# Adafruit_TXB0104.net
KiCad netlist of a schematic drawn in EAGLE
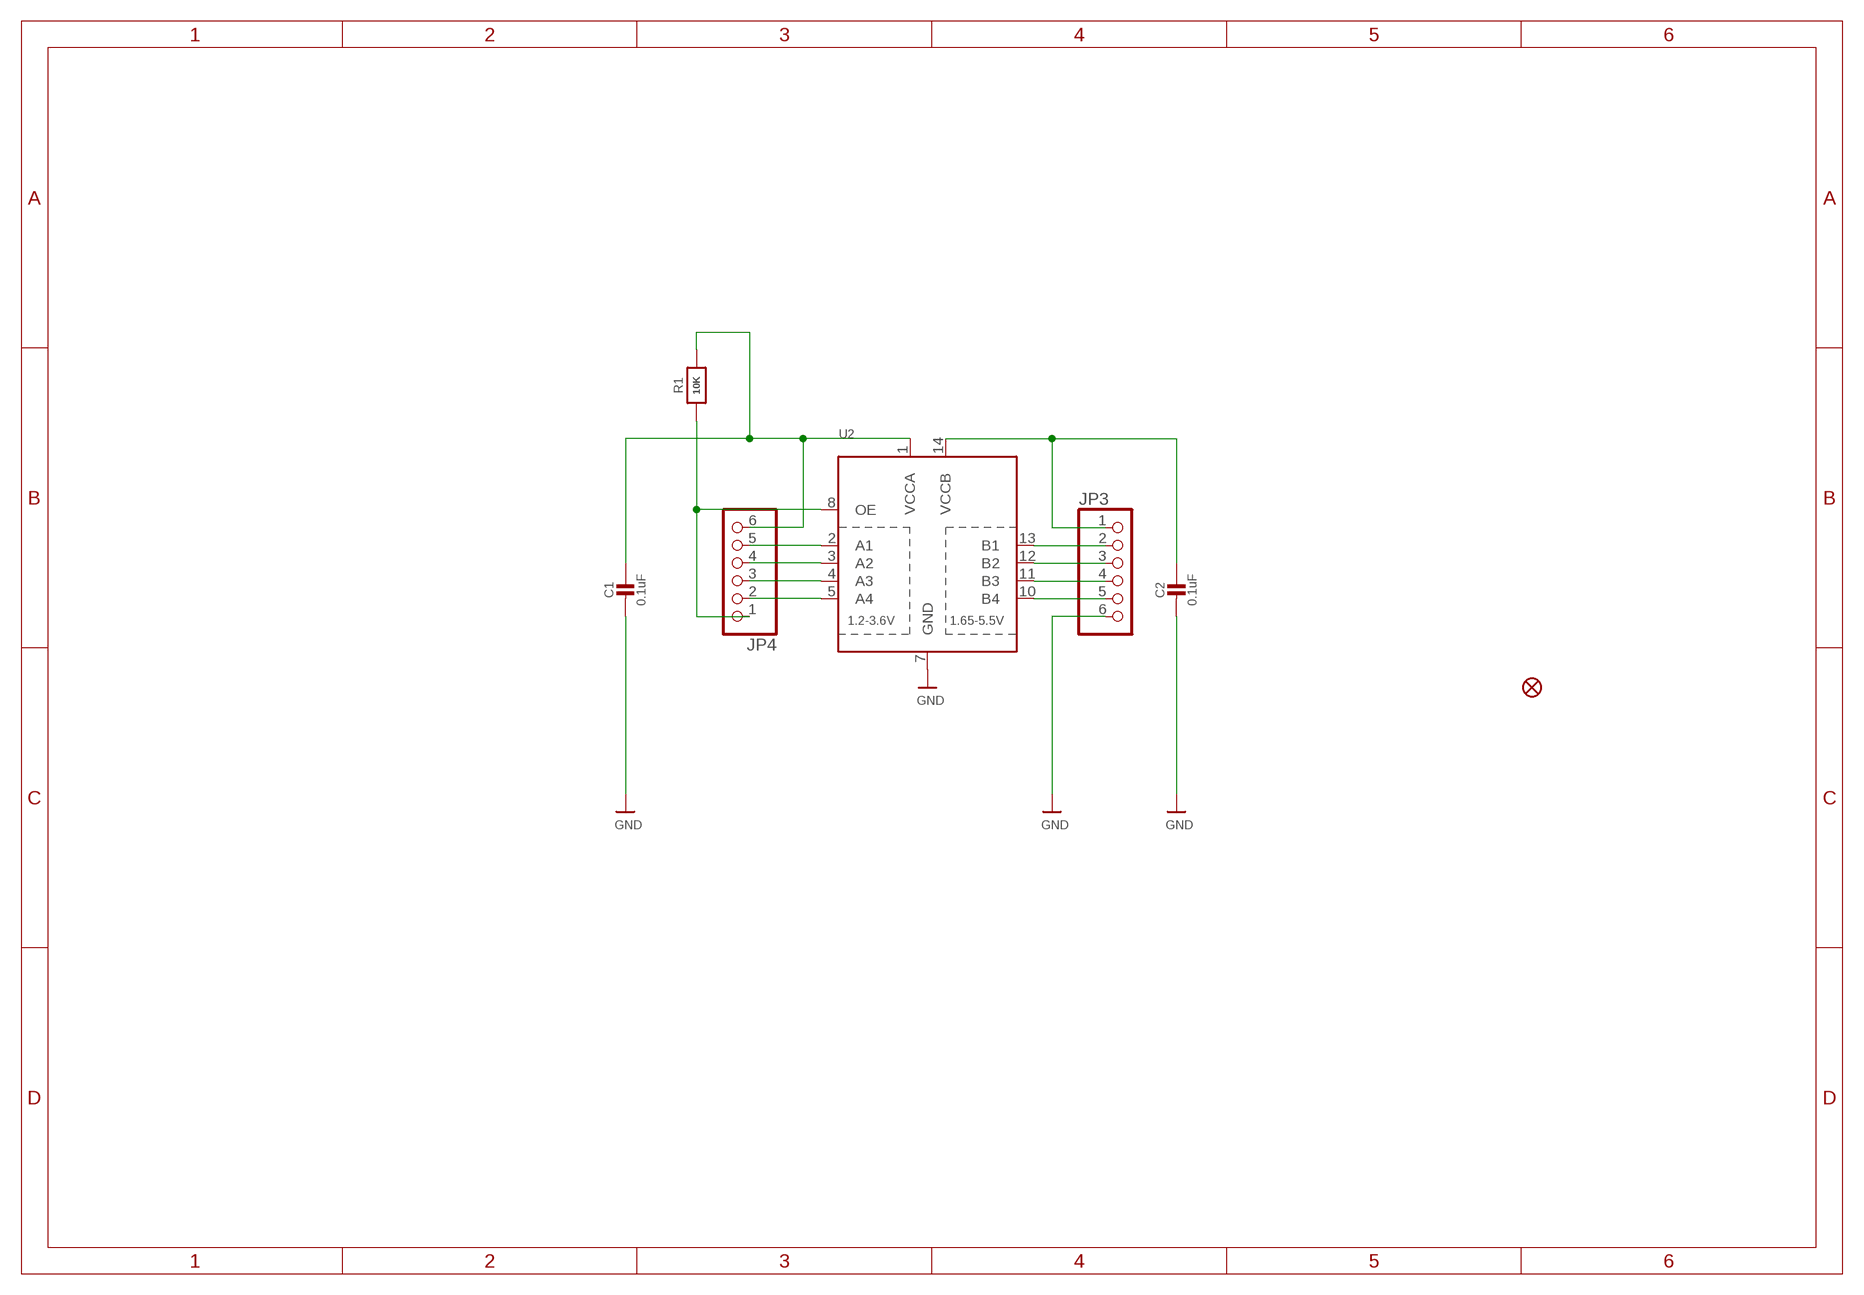
[diagram p0: schematic, sheet 1]

(export (version "E")
  (design (tool "Eeschema 10.0.6"))
  (components
    (comp (ref "C1")
      (value "0.1uF")
      (footprint "eagle-import:0805-NO")
      (libsource (lib "eagle-import") (part "CAP_CERAMIC0805-NOOUTLINE"))
    )
    (comp (ref "C2")
      (value "0.1uF")
      (footprint "eagle-import:0805-NO")
      (libsource (lib "eagle-import") (part "CAP_CERAMIC0805-NOOUTLINE"))
    )
    (comp (ref "JP3")
      (value "PINHD-1X6CB")
      (footprint "eagle-import:1X06-CLEANBIG")
      (libsource (lib "eagle-import") (part "PINHD-1X6CB"))
    )
    (comp (ref "JP4")
      (value "PINHD-1X6CB")
      (footprint "eagle-import:1X06-CLEANBIG")
      (libsource (lib "eagle-import") (part "PINHD-1X6CB"))
    )
    (comp (ref "R1")
      (value "10K")
      (footprint "eagle-import:0805-NO")
      (libsource (lib "eagle-import") (part "RESISTOR0805_NOOUTLINE"))
    )
    (comp (ref "U$5")
      (value "FIDUCIAL_1MM")
      (footprint "eagle-import:FIDUCIAL_1MM")
      (libsource (lib "eagle-import") (part "FIDUCIAL_1MM"))
    )
    (comp (ref "U2")
      (value "TXB0104PWR")
      (footprint "eagle-import:TSSOP14")
      (libsource (lib "eagle-import") (part "TXB0104PWR"))
    )
  )
  (nets
    (net (code "1") (name "GND") (class "Default")
      (node (ref "C1") (pin "2") (pinfunction "2_2") (pintype "passive"))
      (node (ref "C2") (pin "2") (pinfunction "2_2") (pintype "passive"))
      (node (ref "JP3") (pin "6") (pinfunction "6_6") (pintype "passive"))
      (node (ref "U2") (pin "7") (pinfunction "GND_7") (pintype "bidirectional"))
    )
    (net (code "2") (name "Net-(U2-A1)") (class "Default")
      (node (ref "JP4") (pin "5") (pinfunction "5_5") (pintype "passive"))
      (node (ref "U2") (pin "2") (pinfunction "A1_2") (pintype "bidirectional"))
    )
    (net (code "3") (name "Net-(U2-A2)") (class "Default")
      (node (ref "JP4") (pin "4") (pinfunction "4_4") (pintype "passive"))
      (node (ref "U2") (pin "3") (pinfunction "A2_3") (pintype "bidirectional"))
    )
    (net (code "4") (name "Net-(U2-A3)") (class "Default")
      (node (ref "JP4") (pin "3") (pinfunction "3_3") (pintype "passive"))
      (node (ref "U2") (pin "4") (pinfunction "A3_4") (pintype "bidirectional"))
    )
    (net (code "5") (name "Net-(U2-A4)") (class "Default")
      (node (ref "JP4") (pin "2") (pinfunction "2_2") (pintype "passive"))
      (node (ref "U2") (pin "5") (pinfunction "A4_5") (pintype "bidirectional"))
    )
    (net (code "6") (name "Net-(U2-B1)") (class "Default")
      (node (ref "JP3") (pin "2") (pinfunction "2_2") (pintype "passive"))
      (node (ref "U2") (pin "13") (pinfunction "B1_13") (pintype "bidirectional"))
    )
    (net (code "7") (name "Net-(U2-B2)") (class "Default")
      (node (ref "JP3") (pin "3") (pinfunction "3_3") (pintype "passive"))
      (node (ref "U2") (pin "12") (pinfunction "B2_12") (pintype "bidirectional"))
    )
    (net (code "8") (name "Net-(U2-B3)") (class "Default")
      (node (ref "JP3") (pin "4") (pinfunction "4_4") (pintype "passive"))
      (node (ref "U2") (pin "11") (pinfunction "B3_11") (pintype "bidirectional"))
    )
    (net (code "9") (name "Net-(U2-B4)") (class "Default")
      (node (ref "JP3") (pin "5") (pinfunction "5_5") (pintype "passive"))
      (node (ref "U2") (pin "10") (pinfunction "B4_10") (pintype "bidirectional"))
    )
    (net (code "10") (name "Net-(U2-OE)") (class "Default")
      (node (ref "JP4") (pin "1") (pinfunction "1_1") (pintype "passive"))
      (node (ref "R1") (pin "1") (pinfunction "1_1") (pintype "passive"))
      (node (ref "U2") (pin "8") (pinfunction "OE_8") (pintype "bidirectional"))
    )
    (net (code "11") (name "Net-(U2-VCCA)") (class "Default")
      (node (ref "C1") (pin "1") (pinfunction "1_1") (pintype "passive"))
      (node (ref "JP4") (pin "6") (pinfunction "6_6") (pintype "passive"))
      (node (ref "R1") (pin "2") (pinfunction "2_2") (pintype "passive"))
      (node (ref "U2") (pin "1") (pinfunction "VCCA_1") (pintype "bidirectional"))
    )
    (net (code "12") (name "Net-(U2-VCCB)") (class "Default")
      (node (ref "C2") (pin "1") (pinfunction "1_1") (pintype "passive"))
      (node (ref "JP3") (pin "1") (pinfunction "1_1") (pintype "passive"))
      (node (ref "U2") (pin "14") (pinfunction "VCCB_14") (pintype "bidirectional"))
    )
  )
)
